# Extport.net
KiCad netlist of a schematic drawn in Altium Designer
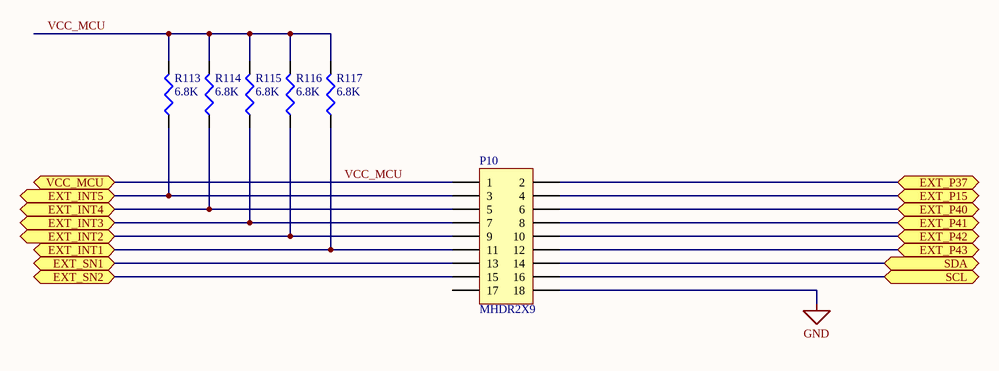
[diagram p0: Extport.SchDoc]

(export (version "E")
  (design (tool "Eeschema 10.0.6"))
  (components
    (comp (ref "P10")
      (value "MHDR2X9")
      (footprint "MHDR2X9")
      (description "Header, 9-Pin, Dual row")
      (fields (field (name "PUBLISHER") "Altium Limited"))
      (libsource (lib "Miscellaneous Connectors") (part "MHDR2X9"))
    )
    (comp (ref "R113")
      (value "6.8K")
      (footprint "clock:0603")
      (description "Resistor")
      (fields (field (name "Comment") "Res3") (field (name "PUBLISHER") "Altium Limited"))
      (libsource (lib "Miscellaneous Devices") (part "Res3"))
    )
    (comp (ref "R114")
      (value "6.8K")
      (footprint "clock:0603")
      (description "Resistor")
      (fields (field (name "Comment") "Res3") (field (name "PUBLISHER") "Altium Limited"))
      (libsource (lib "Miscellaneous Devices") (part "Res3"))
    )
    (comp (ref "R115")
      (value "6.8K")
      (footprint "clock:0603")
      (description "Resistor")
      (fields (field (name "Comment") "Res3") (field (name "PUBLISHER") "Altium Limited"))
      (libsource (lib "Miscellaneous Devices") (part "Res3"))
    )
    (comp (ref "R116")
      (value "6.8K")
      (footprint "clock:0603")
      (description "Resistor")
      (fields (field (name "Comment") "Res3") (field (name "PUBLISHER") "Altium Limited"))
      (libsource (lib "Miscellaneous Devices") (part "Res3"))
    )
    (comp (ref "R117")
      (value "6.8K")
      (footprint "clock:0603")
      (description "Resistor")
      (fields (field (name "Comment") "Res3") (field (name "PUBLISHER") "Altium Limited"))
      (libsource (lib "Miscellaneous Devices") (part "Res3"))
    )
  )
  (nets
    (net (code "1") (name "/EXT_INT1") (class "Default")
      (node (ref "P10") (pin "11") (pinfunction "11_11") (pintype "passive"))
      (node (ref "R117") (pin "1") (pinfunction "1_1") (pintype "passive"))
    )
    (net (code "2") (name "/EXT_INT2") (class "Default")
      (node (ref "P10") (pin "9") (pinfunction "9_9") (pintype "passive"))
      (node (ref "R116") (pin "1") (pinfunction "1_1") (pintype "passive"))
    )
    (net (code "3") (name "/EXT_INT3") (class "Default")
      (node (ref "P10") (pin "7") (pinfunction "7_7") (pintype "passive"))
      (node (ref "R115") (pin "1") (pinfunction "1_1") (pintype "passive"))
    )
    (net (code "4") (name "/EXT_INT4") (class "Default")
      (node (ref "P10") (pin "5") (pinfunction "5_5") (pintype "passive"))
      (node (ref "R114") (pin "1") (pinfunction "1_1") (pintype "passive"))
    )
    (net (code "5") (name "/EXT_INT5") (class "Default")
      (node (ref "P10") (pin "3") (pinfunction "3_3") (pintype "passive"))
      (node (ref "R113") (pin "1") (pinfunction "1_1") (pintype "passive"))
    )
    (net (code "6") (name "/EXT_P15") (class "Default")
      (node (ref "P10") (pin "4") (pinfunction "4_4") (pintype "passive"))
    )
    (net (code "7") (name "/EXT_P37") (class "Default")
      (node (ref "P10") (pin "2") (pinfunction "2_2") (pintype "passive"))
    )
    (net (code "8") (name "/EXT_P40") (class "Default")
      (node (ref "P10") (pin "6") (pinfunction "6_6") (pintype "passive"))
    )
    (net (code "9") (name "/EXT_P41") (class "Default")
      (node (ref "P10") (pin "8") (pinfunction "8_8") (pintype "passive"))
    )
    (net (code "10") (name "/EXT_P42") (class "Default")
      (node (ref "P10") (pin "10") (pinfunction "10_10") (pintype "passive"))
    )
    (net (code "11") (name "/EXT_P43") (class "Default")
      (node (ref "P10") (pin "12") (pinfunction "12_12") (pintype "passive"))
    )
    (net (code "12") (name "/EXT_SN1") (class "Default")
      (node (ref "P10") (pin "13") (pinfunction "13_13") (pintype "passive"))
    )
    (net (code "13") (name "/EXT_SN2") (class "Default")
      (node (ref "P10") (pin "15") (pinfunction "15_15") (pintype "passive"))
    )
    (net (code "14") (name "/SCL") (class "Default")
      (node (ref "P10") (pin "16") (pinfunction "16_16") (pintype "passive"))
    )
    (net (code "15") (name "/SDA") (class "Default")
      (node (ref "P10") (pin "14") (pinfunction "14_14") (pintype "passive"))
    )
    (net (code "16") (name "/VCC_MCU") (class "Default")
      (node (ref "P10") (pin "1") (pinfunction "1_1") (pintype "passive"))
      (node (ref "R113") (pin "2") (pinfunction "2_2") (pintype "passive"))
      (node (ref "R114") (pin "2") (pinfunction "2_2") (pintype "passive"))
      (node (ref "R115") (pin "2") (pinfunction "2_2") (pintype "passive"))
      (node (ref "R116") (pin "2") (pinfunction "2_2") (pintype "passive"))
      (node (ref "R117") (pin "2") (pinfunction "2_2") (pintype "passive"))
    )
    (net (code "17") (name "GND") (class "Default")
      (node (ref "P10") (pin "18") (pinfunction "18_18") (pintype "passive"))
    )
    (net (code "18") (name "unconnected-(P10-Pad17)") (class "Default")
      (node (ref "P10") (pin "17") (pinfunction "17_17") (pintype "passive"))
    )
  )
)
